# 5watch.net
KiCad netlist of a schematic drawn in EAGLE
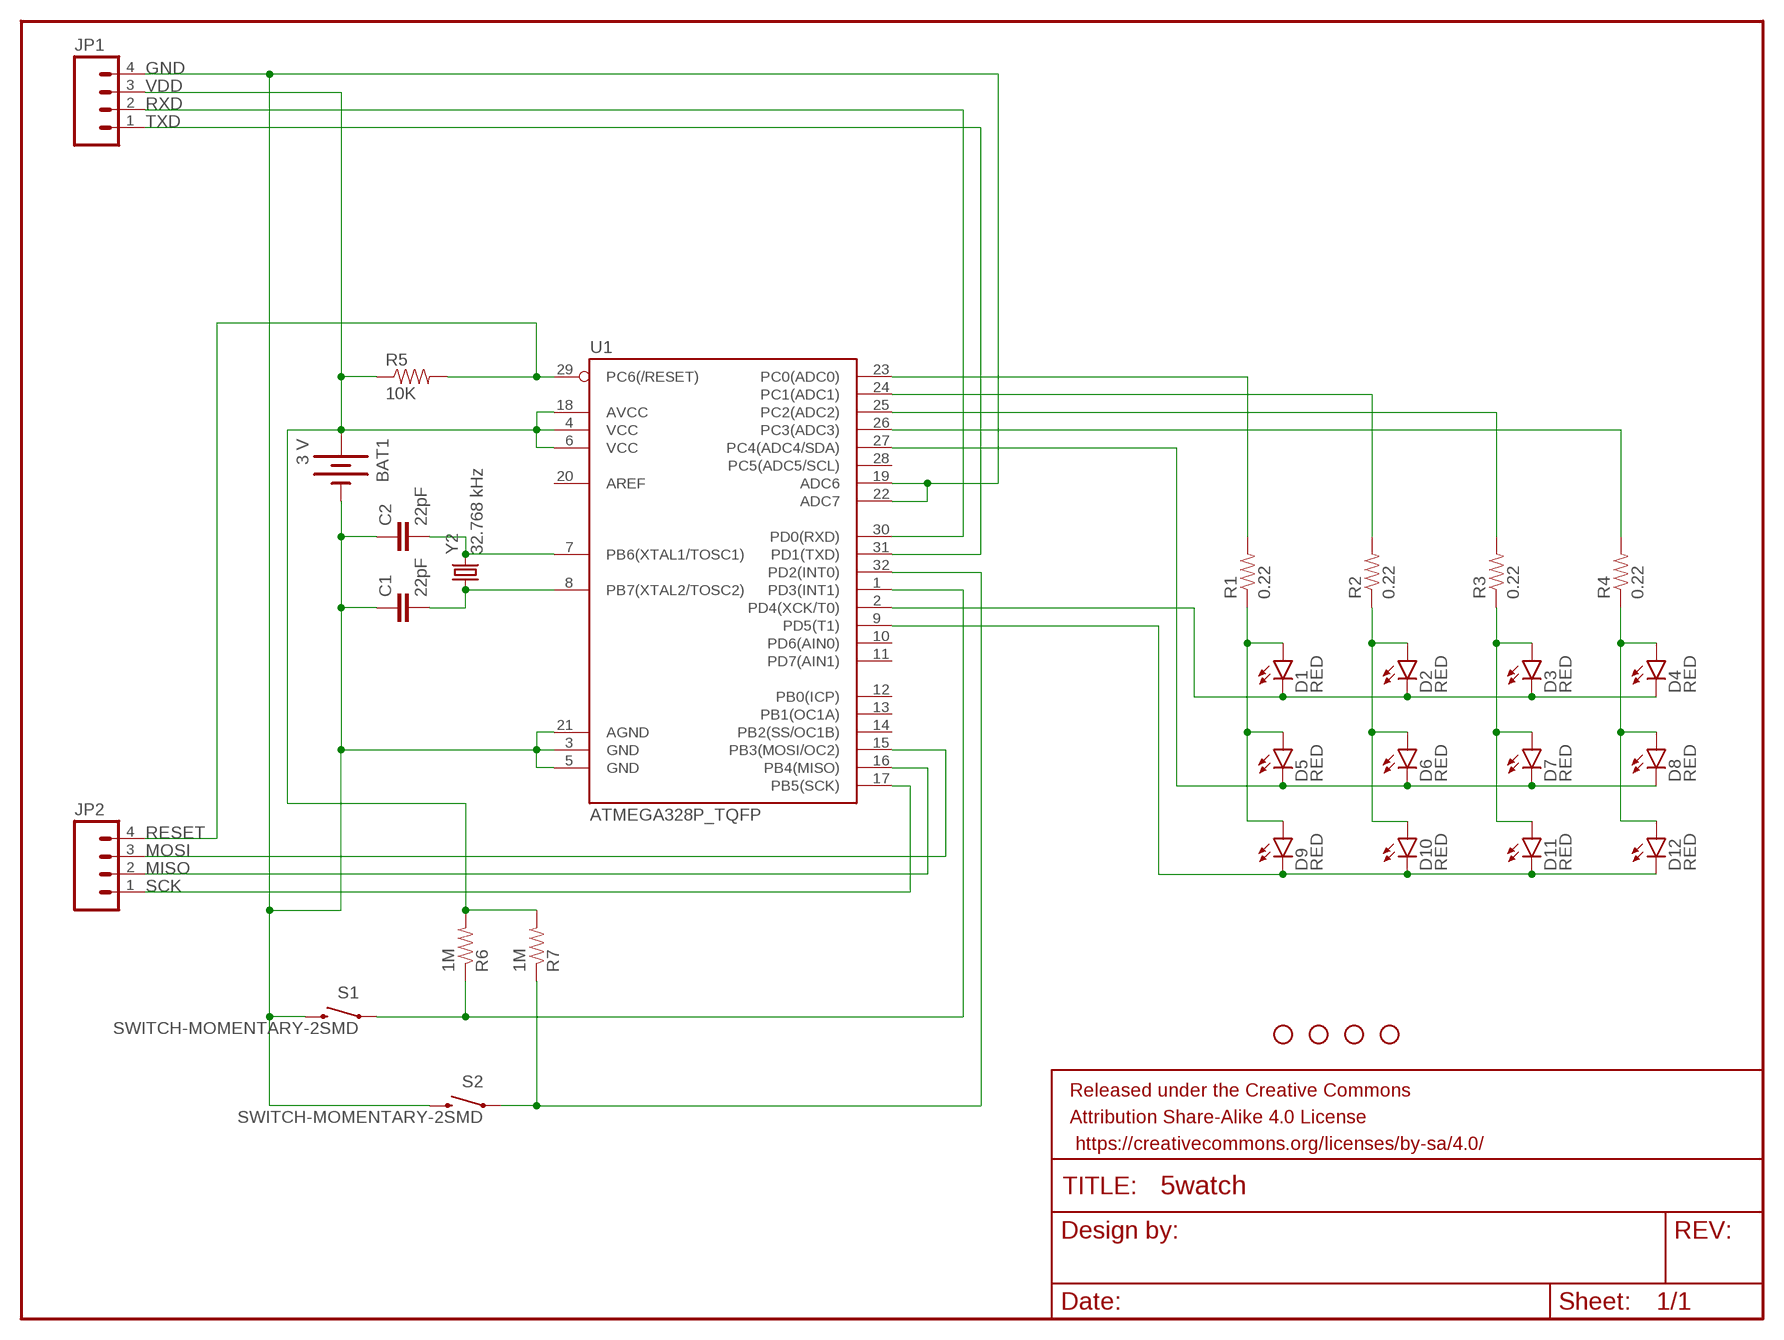
[diagram p0: schematic, sheet 1]

(export (version "E")
  (design (tool "Eeschema 10.0.6"))
  (components
    (comp (ref "BAT1")
      (value "3 V")
      (footprint "eagle-import:BATTCON_20MM_4LEGS")
      (libsource (lib "eagle-import") (part "BATTERY20MM_4LEGS"))
    )
    (comp (ref "C1")
      (value "22pF")
      (footprint "eagle-import:0603-CAP")
      (libsource (lib "eagle-import") (part "22PF-50V-5%(0603)"))
    )
    (comp (ref "C2")
      (value "22pF")
      (footprint "eagle-import:0603-CAP")
      (libsource (lib "eagle-import") (part "22PF-50V-5%(0603)"))
    )
    (comp (ref "D1")
      (value "RED")
      (footprint "eagle-import:LED-1206")
      (libsource (lib "eagle-import") (part "LED-RED1206"))
    )
    (comp (ref "D2")
      (value "RED")
      (footprint "eagle-import:LED-1206")
      (libsource (lib "eagle-import") (part "LED-RED1206"))
    )
    (comp (ref "D3")
      (value "RED")
      (footprint "eagle-import:LED-1206")
      (libsource (lib "eagle-import") (part "LED-RED1206"))
    )
    (comp (ref "D4")
      (value "RED")
      (footprint "eagle-import:LED-1206")
      (libsource (lib "eagle-import") (part "LED-RED1206"))
    )
    (comp (ref "D5")
      (value "RED")
      (footprint "eagle-import:LED-1206")
      (libsource (lib "eagle-import") (part "LED-RED1206"))
    )
    (comp (ref "D6")
      (value "RED")
      (footprint "eagle-import:LED-1206")
      (libsource (lib "eagle-import") (part "LED-RED1206"))
    )
    (comp (ref "D7")
      (value "RED")
      (footprint "eagle-import:LED-1206")
      (libsource (lib "eagle-import") (part "LED-RED1206"))
    )
    (comp (ref "D8")
      (value "RED")
      (footprint "eagle-import:LED-1206")
      (libsource (lib "eagle-import") (part "LED-RED1206"))
    )
    (comp (ref "D9")
      (value "RED")
      (footprint "eagle-import:LED-1206")
      (libsource (lib "eagle-import") (part "LED-RED1206"))
    )
    (comp (ref "D10")
      (value "RED")
      (footprint "eagle-import:LED-1206")
      (libsource (lib "eagle-import") (part "LED-RED1206"))
    )
    (comp (ref "D11")
      (value "RED")
      (footprint "eagle-import:LED-1206")
      (libsource (lib "eagle-import") (part "LED-RED1206"))
    )
    (comp (ref "D12")
      (value "RED")
      (footprint "eagle-import:LED-1206")
      (libsource (lib "eagle-import") (part "LED-RED1206"))
    )
    (comp (ref "FRAME1")
      (value "FRAME-LETTER")
      (footprint "eagle-import:CREATIVE_COMMONS")
      (libsource (lib "eagle-import") (part "FRAME-LETTER"))
    )
    (comp (ref "JP1")
      (value "M04NO_SILK_ALL_ROUND")
      (footprint "eagle-import:1X04_NO_SILK_ALL_ROUND")
      (libsource (lib "eagle-import") (part "M04NO_SILK_ALL_ROUND"))
    )
    (comp (ref "JP2")
      (value "M04NO_SILK_ALL_ROUND")
      (footprint "eagle-import:1X04_NO_SILK_ALL_ROUND")
      (libsource (lib "eagle-import") (part "M04NO_SILK_ALL_ROUND"))
    )
    (comp (ref "R1")
      (value "0.22")
      (footprint "eagle-import:0805")
      (libsource (lib "eagle-import") (part "0.22OHM-1/4W-1%(0805)"))
    )
    (comp (ref "R2")
      (value "0.22")
      (footprint "eagle-import:0805")
      (libsource (lib "eagle-import") (part "0.22OHM-1/4W-1%(0805)"))
    )
    (comp (ref "R3")
      (value "0.22")
      (footprint "eagle-import:0805")
      (libsource (lib "eagle-import") (part "0.22OHM-1/4W-1%(0805)"))
    )
    (comp (ref "R4")
      (value "0.22")
      (footprint "eagle-import:0805")
      (libsource (lib "eagle-import") (part "0.22OHM-1/4W-1%(0805)"))
    )
    (comp (ref "R5")
      (value "10K")
      (footprint "eagle-import:0603-RES")
      (libsource (lib "eagle-import") (part "10KOHM-1/10W-1%(0603)0603"))
    )
    (comp (ref "R6")
      (value "1M")
      (footprint "eagle-import:0603-RES")
      (libsource (lib "eagle-import") (part "1MOHM-1/10W-1%(0603)"))
    )
    (comp (ref "R7")
      (value "1M")
      (footprint "eagle-import:0603-RES")
      (libsource (lib "eagle-import") (part "1MOHM-1/10W-1%(0603)"))
    )
    (comp (ref "S1")
      (value "SWITCH-MOMENTARY-2SMD")
      (footprint "eagle-import:TACTILE-SWITCH-SMD")
      (libsource (lib "eagle-import") (part "SWITCH-MOMENTARY-2SMD"))
    )
    (comp (ref "S2")
      (value "SWITCH-MOMENTARY-2SMD")
      (footprint "eagle-import:TACTILE-SWITCH-SMD")
      (libsource (lib "eagle-import") (part "SWITCH-MOMENTARY-2SMD"))
    )
    (comp (ref "STANDOFF1")
      (value "STAND-OFF")
      (footprint "eagle-import:STAND-OFF")
      (libsource (lib "eagle-import") (part "STAND-OFF"))
    )
    (comp (ref "STANDOFF2")
      (value "STAND-OFF")
      (footprint "eagle-import:STAND-OFF")
      (libsource (lib "eagle-import") (part "STAND-OFF"))
    )
    (comp (ref "STANDOFF3")
      (value "STAND-OFF")
      (footprint "eagle-import:STAND-OFF")
      (libsource (lib "eagle-import") (part "STAND-OFF"))
    )
    (comp (ref "STANDOFF4")
      (value "STAND-OFF")
      (footprint "eagle-import:STAND-OFF")
      (libsource (lib "eagle-import") (part "STAND-OFF"))
    )
    (comp (ref "U1")
      (value "ATMEGA328P_TQFP")
      (footprint "eagle-import:TQFP32-08")
      (libsource (lib "eagle-import") (part "ATMEGA328P_TQFP"))
    )
    (comp (ref "Y2")
      (value "32.768 kHz")
      (footprint "eagle-import:CRYSTAL-32KHZ-SMD")
      (libsource (lib "eagle-import") (part "CRYSTAL32-SMD"))
    )
  )
  (nets
    (net (code "1") (name "/GND") (class "Default")
      (node (ref "BAT1") (pin "2") (pinfunction "-_2") (pintype "power_in"))
      (node (ref "C1") (pin "1") (pinfunction "1_1") (pintype "passive"))
      (node (ref "C2") (pin "1") (pinfunction "1_1") (pintype "passive"))
      (node (ref "JP1") (pin "4") (pinfunction "4_4") (pintype "passive"))
      (node (ref "S1") (pin "3") (pinfunction "2_3") (pintype "passive"))
      (node (ref "S2") (pin "3") (pinfunction "2_3") (pintype "passive"))
      (node (ref "U1") (pin "19") (pinfunction "ADC6_19") (pintype "bidirectional"))
      (node (ref "U1") (pin "21") (pinfunction "AGND_21") (pintype "bidirectional"))
      (node (ref "U1") (pin "22") (pinfunction "ADC7_22") (pintype "bidirectional"))
      (node (ref "U1") (pin "3") (pinfunction "GND_3") (pintype "bidirectional"))
      (node (ref "U1") (pin "5") (pinfunction "GND_5") (pintype "bidirectional"))
    )
    (net (code "2") (name "/MISO") (class "Default")
      (node (ref "JP2") (pin "2") (pinfunction "2_2") (pintype "passive"))
      (node (ref "U1") (pin "16") (pinfunction "PB4(MISO)_16") (pintype "bidirectional"))
    )
    (net (code "3") (name "/MOSI") (class "Default")
      (node (ref "JP2") (pin "3") (pinfunction "3_3") (pintype "passive"))
      (node (ref "U1") (pin "15") (pinfunction "PB3(MOSI/OC2)_15") (pintype "bidirectional"))
    )
    (net (code "4") (name "/RESET") (class "Default")
      (node (ref "JP2") (pin "4") (pinfunction "4_4") (pintype "passive"))
      (node (ref "R5") (pin "2") (pinfunction "2_2") (pintype "passive"))
      (node (ref "U1") (pin "29") (pinfunction "PC6(/RESET)_29") (pintype "bidirectional"))
    )
    (net (code "5") (name "/RXD") (class "Default")
      (node (ref "JP1") (pin "2") (pinfunction "2_2") (pintype "passive"))
      (node (ref "U1") (pin "30") (pinfunction "PD0(RXD)_30") (pintype "bidirectional"))
    )
    (net (code "6") (name "/SCK") (class "Default")
      (node (ref "JP2") (pin "1") (pinfunction "1_1") (pintype "passive"))
      (node (ref "U1") (pin "17") (pinfunction "PB5(SCK)_17") (pintype "bidirectional"))
    )
    (net (code "7") (name "/TXD") (class "Default")
      (node (ref "JP1") (pin "1") (pinfunction "1_1") (pintype "passive"))
      (node (ref "U1") (pin "31") (pinfunction "PD1(TXD)_31") (pintype "bidirectional"))
    )
    (net (code "8") (name "/VDD") (class "Default")
      (node (ref "BAT1") (pin "1") (pinfunction "+_1") (pintype "power_in"))
      (node (ref "JP1") (pin "3") (pinfunction "3_3") (pintype "passive"))
      (node (ref "R5") (pin "1") (pinfunction "1_1") (pintype "passive"))
      (node (ref "R6") (pin "2") (pinfunction "2_2") (pintype "passive"))
      (node (ref "R7") (pin "2") (pinfunction "2_2") (pintype "passive"))
      (node (ref "U1") (pin "18") (pinfunction "AVCC_18") (pintype "bidirectional"))
      (node (ref "U1") (pin "4") (pinfunction "VCC_4") (pintype "bidirectional"))
      (node (ref "U1") (pin "6") (pinfunction "VCC_6") (pintype "bidirectional"))
    )
    (net (code "9") (name "Net-(D1-PadA)") (class "Default")
      (node (ref "D1") (pin "A") (pinfunction "A_A") (pintype "passive"))
      (node (ref "D5") (pin "A") (pinfunction "A_A") (pintype "passive"))
      (node (ref "D9") (pin "A") (pinfunction "A_A") (pintype "passive"))
      (node (ref "R1") (pin "1") (pinfunction "1_1") (pintype "passive"))
    )
    (net (code "10") (name "Net-(D10-PadA)") (class "Default")
      (node (ref "D10") (pin "A") (pinfunction "A_A") (pintype "passive"))
      (node (ref "D2") (pin "A") (pinfunction "A_A") (pintype "passive"))
      (node (ref "D6") (pin "A") (pinfunction "A_A") (pintype "passive"))
      (node (ref "R2") (pin "1") (pinfunction "1_1") (pintype "passive"))
    )
    (net (code "11") (name "Net-(D11-PadA)") (class "Default")
      (node (ref "D11") (pin "A") (pinfunction "A_A") (pintype "passive"))
      (node (ref "D3") (pin "A") (pinfunction "A_A") (pintype "passive"))
      (node (ref "D7") (pin "A") (pinfunction "A_A") (pintype "passive"))
      (node (ref "R3") (pin "1") (pinfunction "1_1") (pintype "passive"))
    )
    (net (code "12") (name "Net-(D12-PadA)") (class "Default")
      (node (ref "D12") (pin "A") (pinfunction "A_A") (pintype "passive"))
      (node (ref "D4") (pin "A") (pinfunction "A_A") (pintype "passive"))
      (node (ref "D8") (pin "A") (pinfunction "A_A") (pintype "passive"))
      (node (ref "R4") (pin "1") (pinfunction "1_1") (pintype "passive"))
    )
    (net (code "13") (name "Net-(U1-PB6(XTAL1{slash}TOSC1))") (class "Default")
      (node (ref "C2") (pin "2") (pinfunction "2_2") (pintype "passive"))
      (node (ref "U1") (pin "7") (pinfunction "PB6(XTAL1/TOSC1)_7") (pintype "bidirectional"))
      (node (ref "Y2") (pin "X2") (pinfunction "2_X2") (pintype "passive"))
    )
    (net (code "14") (name "Net-(U1-PB7(XTAL2{slash}TOSC2))") (class "Default")
      (node (ref "C1") (pin "2") (pinfunction "2_2") (pintype "passive"))
      (node (ref "U1") (pin "8") (pinfunction "PB7(XTAL2/TOSC2)_8") (pintype "bidirectional"))
      (node (ref "Y2") (pin "X1") (pinfunction "1_X1") (pintype "passive"))
    )
    (net (code "15") (name "Net-(U1-PC0(ADC0))") (class "Default")
      (node (ref "R1") (pin "2") (pinfunction "2_2") (pintype "passive"))
      (node (ref "U1") (pin "23") (pinfunction "PC0(ADC0)_23") (pintype "bidirectional"))
    )
    (net (code "16") (name "Net-(U1-PC1(ADC1))") (class "Default")
      (node (ref "R2") (pin "2") (pinfunction "2_2") (pintype "passive"))
      (node (ref "U1") (pin "24") (pinfunction "PC1(ADC1)_24") (pintype "bidirectional"))
    )
    (net (code "17") (name "Net-(U1-PC2(ADC2))") (class "Default")
      (node (ref "R3") (pin "2") (pinfunction "2_2") (pintype "passive"))
      (node (ref "U1") (pin "25") (pinfunction "PC2(ADC2)_25") (pintype "bidirectional"))
    )
    (net (code "18") (name "Net-(U1-PC3(ADC3))") (class "Default")
      (node (ref "R4") (pin "2") (pinfunction "2_2") (pintype "passive"))
      (node (ref "U1") (pin "26") (pinfunction "PC3(ADC3)_26") (pintype "bidirectional"))
    )
    (net (code "19") (name "Net-(U1-PC4(ADC4{slash}SDA))") (class "Default")
      (node (ref "D5") (pin "C") (pinfunction "C_C") (pintype "passive"))
      (node (ref "D6") (pin "C") (pinfunction "C_C") (pintype "passive"))
      (node (ref "D7") (pin "C") (pinfunction "C_C") (pintype "passive"))
      (node (ref "D8") (pin "C") (pinfunction "C_C") (pintype "passive"))
      (node (ref "U1") (pin "27") (pinfunction "PC4(ADC4/SDA)_27") (pintype "bidirectional"))
    )
    (net (code "20") (name "Net-(U1-PD2(INT0))") (class "Default")
      (node (ref "R7") (pin "1") (pinfunction "1_1") (pintype "passive"))
      (node (ref "S2") (pin "1") (pinfunction "1_1") (pintype "passive"))
      (node (ref "U1") (pin "32") (pinfunction "PD2(INT0)_32") (pintype "bidirectional"))
    )
    (net (code "21") (name "Net-(U1-PD3(INT1))") (class "Default")
      (node (ref "R6") (pin "1") (pinfunction "1_1") (pintype "passive"))
      (node (ref "S1") (pin "1") (pinfunction "1_1") (pintype "passive"))
      (node (ref "U1") (pin "1") (pinfunction "PD3(INT1)_1") (pintype "bidirectional"))
    )
    (net (code "22") (name "Net-(U1-PD4(XCK{slash}T0))") (class "Default")
      (node (ref "D1") (pin "C") (pinfunction "C_C") (pintype "passive"))
      (node (ref "D2") (pin "C") (pinfunction "C_C") (pintype "passive"))
      (node (ref "D3") (pin "C") (pinfunction "C_C") (pintype "passive"))
      (node (ref "D4") (pin "C") (pinfunction "C_C") (pintype "passive"))
      (node (ref "U1") (pin "2") (pinfunction "PD4(XCK/T0)_2") (pintype "bidirectional"))
    )
    (net (code "23") (name "Net-(U1-PD5(T1))") (class "Default")
      (node (ref "D10") (pin "C") (pinfunction "C_C") (pintype "passive"))
      (node (ref "D11") (pin "C") (pinfunction "C_C") (pintype "passive"))
      (node (ref "D12") (pin "C") (pinfunction "C_C") (pintype "passive"))
      (node (ref "D9") (pin "C") (pinfunction "C_C") (pintype "passive"))
      (node (ref "U1") (pin "9") (pinfunction "PD5(T1)_9") (pintype "bidirectional"))
    )
    (net (code "24") (name "unconnected-(U1-AREF-Pad20)") (class "Default")
      (node (ref "U1") (pin "20") (pinfunction "AREF_20") (pintype "bidirectional"))
    )
    (net (code "25") (name "unconnected-(U1-PB0(ICP)-Pad12)") (class "Default")
      (node (ref "U1") (pin "12") (pinfunction "PB0(ICP)_12") (pintype "bidirectional"))
    )
    (net (code "26") (name "unconnected-(U1-PB1(OC1A)-Pad13)") (class "Default")
      (node (ref "U1") (pin "13") (pinfunction "PB1(OC1A)_13") (pintype "bidirectional"))
    )
    (net (code "27") (name "unconnected-(U1-PB2(SS{slash}OC1B)-Pad14)") (class "Default")
      (node (ref "U1") (pin "14") (pinfunction "PB2(SS/OC1B)_14") (pintype "bidirectional"))
    )
    (net (code "28") (name "unconnected-(U1-PC5(ADC5{slash}SCL)-Pad28)") (class "Default")
      (node (ref "U1") (pin "28") (pinfunction "PC5(ADC5/SCL)_28") (pintype "bidirectional"))
    )
    (net (code "29") (name "unconnected-(U1-PD6(AIN0)-Pad10)") (class "Default")
      (node (ref "U1") (pin "10") (pinfunction "PD6(AIN0)_10") (pintype "bidirectional"))
    )
    (net (code "30") (name "unconnected-(U1-PD7(AIN1)-Pad11)") (class "Default")
      (node (ref "U1") (pin "11") (pinfunction "PD7(AIN1)_11") (pintype "bidirectional"))
    )
  )
)
